# crypto_blk.net
KiCad netlist of a schematic drawn in Altium Designer
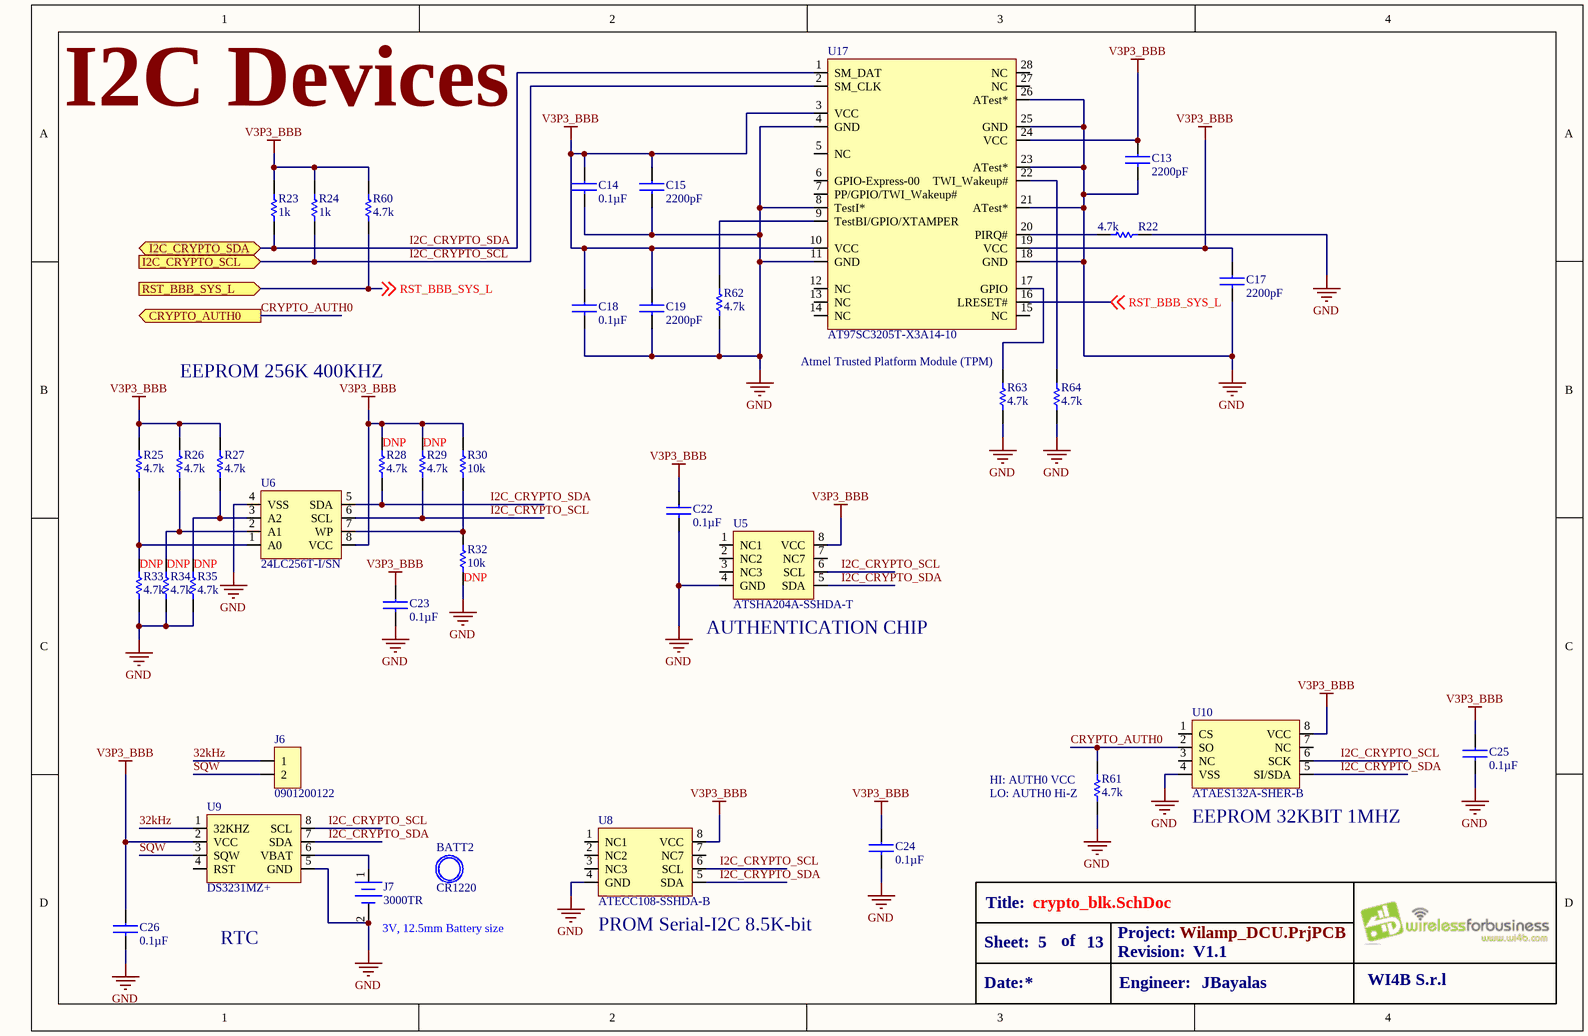
[diagram p0: crypto_blk.SchDoc]

(export (version "E")
  (design (tool "Eeschema 10.0.6"))
  (components
    (comp (ref "BATT2")
      (value "CR1220")
      (description "Coin Cell Battery 35mAh 12.5mm")
      (fields (field (name "MPN") "CR1220"))
      (libsource (lib "Miscellaneous") (part "CR1220"))
    )
    (comp (ref "C13")
      (value "2200pF")
      (footprint "C0805")
      (description "CAP CER 2200PF 50V 10% X7R 0805")
      (fields (field (name "MPN") "08055C222KAT2A"))
      (libsource (lib "Capacitor") (part "08055C222KAT2A"))
    )
    (comp (ref "C14")
      (value "0.1µF")
      (footprint "C0402")
      (description "CAP CER 0.1UF 16V X7R 0402")
      (fields (field (name "MPN") "CL05B104KO3LNNC"))
      (libsource (lib "Capacitor") (part "CL05B104KO3LNNC"))
    )
    (comp (ref "C15")
      (value "2200pF")
      (footprint "C0805")
      (description "CAP CER 2200PF 50V 10% X7R 0805")
      (fields (field (name "MPN") "08055C222KAT2A"))
      (libsource (lib "Capacitor") (part "08055C222KAT2A"))
    )
    (comp (ref "C17")
      (value "2200pF")
      (footprint "C0603")
      (description "CAP CER 2200PF 50V X7R 0603")
      (fields (field (name "MPN") "C0603C222K5RACTU"))
      (libsource (lib "Capacitor") (part "C0603C222K5RACTU"))
    )
    (comp (ref "C18")
      (value "0.1µF")
      (footprint "C0402")
      (description "CAP CER 0.1UF 16V X7R 0402")
      (fields (field (name "MPN") "CL05B104KO3LNNC"))
      (libsource (lib "Capacitor") (part "CL05B104KO3LNNC"))
    )
    (comp (ref "C19")
      (value "2200pF")
      (footprint "C0805")
      (description "CAP CER 2200PF 50V 10% X7R 0805")
      (fields (field (name "MPN") "08055C222KAT2A"))
      (libsource (lib "Capacitor") (part "08055C222KAT2A"))
    )
    (comp (ref "C22")
      (value "0.1µF")
      (footprint "C0402")
      (description "CAP CER 0.1UF 16V X7R 0402")
      (fields (field (name "MPN") "CL05B104KO3LNNC"))
      (libsource (lib "Capacitor") (part "CL05B104KO3LNNC"))
    )
    (comp (ref "C23")
      (value "0.1µF")
      (footprint "C0402")
      (description "CAP CER 0.1UF 16V X7R 0402")
      (fields (field (name "MPN") "CL05B104KO3LNNC"))
      (libsource (lib "Capacitor") (part "CL05B104KO3LNNC"))
    )
    (comp (ref "C24")
      (value "0.1µF")
      (footprint "C0402")
      (description "CAP CER 0.1UF 16V X7R 0402")
      (fields (field (name "MPN") "CL05B104KO3LNNC"))
      (libsource (lib "Capacitor") (part "CL05B104KO3LNNC"))
    )
    (comp (ref "C25")
      (value "0.1µF")
      (footprint "C0402")
      (description "CAP CER 0.1UF 16V X7R 0402")
      (fields (field (name "MPN") "CL05B104KO3LNNC"))
      (libsource (lib "Capacitor") (part "CL05B104KO3LNNC"))
    )
    (comp (ref "C26")
      (value "0.1µF")
      (footprint "C0402")
      (description "CAP CER 0.1UF 16V X7R 0402")
      (fields (field (name "MPN") "CL05B104KO3LNNC"))
      (libsource (lib "Capacitor") (part "CL05B104KO3LNNC"))
    )
    (comp (ref "J6")
      (value "*")
      (footprint "0901200122")
      (description "CONN HEADER 2POS .100\" STR TIN")
      (fields (field (name "MPN") "0901200122"))
      (libsource (lib "Connector") (part "0901200122"))
    )
    (comp (ref "J7")
      (value "3000TR")
      (footprint "3000TR")
      (description "Coin Cell Battery Holders SM COIN CELL B/H")
      (libsource (lib "Connector") (part "3000TR"))
    )
    (comp (ref "R22")
      (value "4.7k")
      (footprint "R0402")
      (description "RES SMD 4.7K OHM 5% 1/16W 0402")
      (fields (field (name "MPN") "RC0402JR-074K7L"))
      (libsource (lib "Res") (part "RC0402JR-074K7L"))
    )
    (comp (ref "R23")
      (value "1k")
      (footprint "R0402")
      (description "RES SMD 1K OHM 1% 1/10W 0402")
      (fields (field (name "MPN") "MCS04020C1001FE000"))
      (libsource (lib "Res") (part "MCS04020C1001FE000"))
    )
    (comp (ref "R24")
      (value "1k")
      (footprint "R0402")
      (description "RES SMD 1K OHM 1% 1/10W 0402")
      (fields (field (name "MPN") "MCS04020C1001FE000"))
      (libsource (lib "Res") (part "MCS04020C1001FE000"))
    )
    (comp (ref "R25")
      (value "4.7k")
      (footprint "R0402")
      (description "RES SMD 4.7K OHM 5% 1/16W 0402")
      (fields (field (name "MPN") "RC0402JR-074K7L"))
      (libsource (lib "Res") (part "RC0402JR-074K7L"))
    )
    (comp (ref "R26")
      (value "4.7k")
      (footprint "R0402")
      (description "RES SMD 4.7K OHM 5% 1/16W 0402")
      (fields (field (name "MPN") "RC0402JR-074K7L"))
      (libsource (lib "Res") (part "RC0402JR-074K7L"))
    )
    (comp (ref "R27")
      (value "4.7k")
      (footprint "R0402")
      (description "RES SMD 4.7K OHM 5% 1/16W 0402")
      (fields (field (name "MPN") "RC0402JR-074K7L"))
      (libsource (lib "Res") (part "RC0402JR-074K7L"))
    )
    (comp (ref "R28")
      (value "4.7k")
      (footprint "R0402")
      (description "RES SMD 4.7K OHM 5% 1/16W 0402")
      (fields (field (name "MPN") "RC0402JR-074K7L") (field (name "LOAD") "DNP"))
      (libsource (lib "Res") (part "RC0402JR-074K7L"))
    )
    (comp (ref "R29")
      (value "4.7k")
      (footprint "R0402")
      (description "RES SMD 4.7K OHM 5% 1/16W 0402")
      (fields (field (name "MPN") "RC0402JR-074K7L") (field (name "LOAD") "DNP"))
      (libsource (lib "Res") (part "RC0402JR-074K7L"))
    )
    (comp (ref "R30")
      (value "10k")
      (footprint "R0402")
      (description "RES SMD 10K OHM 1% 1/5W 0402")
      (fields (field (name "MPN") "CRCW040210K0FKEDHP"))
      (libsource (lib "Res") (part "CRCW040210K0FKEDHP"))
    )
    (comp (ref "R32")
      (value "10k")
      (footprint "R0402")
      (description "RES SMD 10K OHM 1% 1/5W 0402")
      (fields (field (name "MPN") "CRCW040210K0FKEDHP") (field (name "LOAD") "DNP"))
      (libsource (lib "Res") (part "CRCW040210K0FKEDHP"))
    )
    (comp (ref "R33")
      (value "4.7k")
      (footprint "R0402")
      (description "RES SMD 4.7K OHM 5% 1/16W 0402")
      (fields (field (name "MPN") "RC0402JR-074K7L") (field (name "LOAD") "DNP"))
      (libsource (lib "Res") (part "RC0402JR-074K7L"))
    )
    (comp (ref "R34")
      (value "4.7k")
      (footprint "R0402")
      (description "RES SMD 4.7K OHM 5% 1/16W 0402")
      (fields (field (name "MPN") "RC0402JR-074K7L") (field (name "LOAD") "DNP"))
      (libsource (lib "Res") (part "RC0402JR-074K7L"))
    )
    (comp (ref "R35")
      (value "4.7k")
      (footprint "R0402")
      (description "RES SMD 4.7K OHM 5% 1/16W 0402")
      (fields (field (name "MPN") "RC0402JR-074K7L") (field (name "LOAD") "DNP"))
      (libsource (lib "Res") (part "RC0402JR-074K7L"))
    )
    (comp (ref "R60")
      (value "4.7k")
      (footprint "R0402")
      (description "RES SMD 4.7K OHM 5% 1/16W 0402")
      (fields (field (name "MPN") "RC0402JR-074K7L"))
      (libsource (lib "Res") (part "RC0402JR-074K7L"))
    )
    (comp (ref "R61")
      (value "4.7k")
      (footprint "R0402")
      (description "RES SMD 4.7K OHM 5% 1/16W 0402")
      (fields (field (name "MPN") "RC0402JR-074K7L"))
      (libsource (lib "Res") (part "RC0402JR-074K7L"))
    )
    (comp (ref "R62")
      (value "4.7k")
      (footprint "R0402")
      (description "RES SMD 4.7K OHM 5% 1/16W 0402")
      (fields (field (name "MPN") "RC0402JR-074K7L"))
      (libsource (lib "Res") (part "RC0402JR-074K7L"))
    )
    (comp (ref "R63")
      (value "4.7k")
      (footprint "R0402")
      (description "RES SMD 4.7K OHM 5% 1/16W 0402")
      (fields (field (name "MPN") "RC0402JR-074K7L"))
      (libsource (lib "Res") (part "RC0402JR-074K7L"))
    )
    (comp (ref "R64")
      (value "4.7k")
      (footprint "R0402")
      (description "RES SMD 4.7K OHM 5% 1/16W 0402")
      (fields (field (name "MPN") "RC0402JR-074K7L"))
      (libsource (lib "Res") (part "RC0402JR-074K7L"))
    )
    (comp (ref "U5")
      (value "ATSHA204A-SSHDA-T")
      (footprint "SOIC-8")
      (description "IC AUTHENTICATION CHIP 8SOIC")
      (libsource (lib "IC") (part "ATSHA204A-SSHDA-T"))
    )
    (comp (ref "U6")
      (value "24LC256T-I/SN")
      (footprint "SOIC-8")
      (description "IC EEPROM 256K I2C 400KHZ 8SOIC")
      (libsource (lib "IC") (part "24LC256T-I/SN"))
    )
    (comp (ref "U8")
      (value "ATECC108-SSHDA-B")
      (footprint "SOIC-8")
      (description "EEPROM Serial-I2C 8.5K-bit 2.5V/3.3V/5V 8-Pin SOIC Bulk")
      (libsource (lib "IC") (part "ATECC108-SSHDA-B"))
    )
    (comp (ref "U9")
      (value "DS3231MZ+")
      (footprint "SOIC-8")
      (description "IC RTC I2C 8SOIC")
      (libsource (lib "IC") (part "DS3231MZ+"))
    )
    (comp (ref "U10")
      (value "ATAES132A-SHER-B")
      (footprint "SOIC-8")
      (description "IC EEPROM 32KBIT 1MHZ 8SOIC")
      (libsource (lib "IC") (part "ATAES132A-SHER-B"))
    )
    (comp (ref "U17")
      (value "AT97SC3205T-X3A14-10")
      (footprint "TSSOP-28")
      (description "STD COM 12C TPM 4.4 MM TSSOP UEK")
      (libsource (lib "IC") (part "AT97SC3205T-X3A14-10"))
    )
  )
  (nets
    (net (code "1") (name "/32kHz") (class "Default")
      (node (ref "J6") (pin "1") (pinfunction "1_1") (pintype "passive"))
      (node (ref "U9") (pin "1") (pinfunction "32KHZ_1") (pintype "passive"))
    )
    (net (code "2") (name "/CRYPTO_AUTH0") (class "Default")
      (node (ref "R61") (pin "2") (pinfunction "2_2") (pintype "passive"))
      (node (ref "U10") (pin "2") (pinfunction "SO_2") (pintype "passive"))
    )
    (net (code "3") (name "/I2C_CRYPTO_SCL") (class "Default")
      (node (ref "R24") (pin "2") (pinfunction "2_2") (pintype "passive"))
      (node (ref "R29") (pin "1") (pinfunction "1_1") (pintype "passive"))
      (node (ref "U10") (pin "6") (pinfunction "SCK_6") (pintype "passive"))
      (node (ref "U17") (pin "2") (pinfunction "SM_CLK_2") (pintype "passive"))
      (node (ref "U5") (pin "6") (pinfunction "SCL_6") (pintype "passive"))
      (node (ref "U6") (pin "6") (pinfunction "SCL_6") (pintype "passive"))
      (node (ref "U8") (pin "6") (pinfunction "SCL_6") (pintype "passive"))
      (node (ref "U9") (pin "8") (pinfunction "SCL_8") (pintype "passive"))
    )
    (net (code "4") (name "/I2C_CRYPTO_SDA") (class "Default")
      (node (ref "R23") (pin "2") (pinfunction "2_2") (pintype "passive"))
      (node (ref "R28") (pin "1") (pinfunction "1_1") (pintype "passive"))
      (node (ref "U10") (pin "5") (pinfunction "SI/SDA_5") (pintype "passive"))
      (node (ref "U17") (pin "1") (pinfunction "SM_DAT_1") (pintype "passive"))
      (node (ref "U5") (pin "5") (pinfunction "SDA_5") (pintype "passive"))
      (node (ref "U6") (pin "5") (pinfunction "SDA_5") (pintype "passive"))
      (node (ref "U8") (pin "5") (pinfunction "SDA_5") (pintype "passive"))
      (node (ref "U9") (pin "7") (pinfunction "SDA_7") (pintype "passive"))
    )
    (net (code "5") (name "/SQW") (class "Default")
      (node (ref "J6") (pin "2") (pinfunction "2_2") (pintype "passive"))
      (node (ref "U9") (pin "3") (pinfunction "SQW_3") (pintype "passive"))
    )
    (net (code "6") (name "GND") (class "Default")
      (node (ref "C13") (pin "2") (pinfunction "2_2") (pintype "passive"))
      (node (ref "C14") (pin "2") (pinfunction "2_2") (pintype "passive"))
      (node (ref "C15") (pin "2") (pinfunction "2_2") (pintype "passive"))
      (node (ref "C17") (pin "2") (pinfunction "2_2") (pintype "passive"))
      (node (ref "C18") (pin "2") (pinfunction "2_2") (pintype "passive"))
      (node (ref "C19") (pin "2") (pinfunction "2_2") (pintype "passive"))
      (node (ref "C22") (pin "2") (pinfunction "2_2") (pintype "passive"))
      (node (ref "C23") (pin "2") (pinfunction "2_2") (pintype "passive"))
      (node (ref "C24") (pin "2") (pinfunction "2_2") (pintype "passive"))
      (node (ref "C25") (pin "2") (pinfunction "2_2") (pintype "passive"))
      (node (ref "C26") (pin "2") (pinfunction "2_2") (pintype "passive"))
      (node (ref "J7") (pin "2") (pinfunction "-_2") (pintype "passive"))
      (node (ref "R22") (pin "1") (pinfunction "1_1") (pintype "passive"))
      (node (ref "R32") (pin "1") (pinfunction "1_1") (pintype "passive"))
      (node (ref "R33") (pin "1") (pinfunction "1_1") (pintype "passive"))
      (node (ref "R34") (pin "1") (pinfunction "1_1") (pintype "passive"))
      (node (ref "R35") (pin "1") (pinfunction "1_1") (pintype "passive"))
      (node (ref "R61") (pin "1") (pinfunction "1_1") (pintype "passive"))
      (node (ref "R62") (pin "1") (pinfunction "1_1") (pintype "passive"))
      (node (ref "R63") (pin "1") (pinfunction "1_1") (pintype "passive"))
      (node (ref "R64") (pin "1") (pinfunction "1_1") (pintype "passive"))
      (node (ref "U10") (pin "4") (pinfunction "VSS_4") (pintype "passive"))
      (node (ref "U17") (pin "11") (pinfunction "GND_11") (pintype "passive"))
      (node (ref "U17") (pin "18") (pinfunction "GND_18") (pintype "passive"))
      (node (ref "U17") (pin "21") (pinfunction "ATest*_21") (pintype "passive"))
      (node (ref "U17") (pin "23") (pinfunction "ATest*_23") (pintype "passive"))
      (node (ref "U17") (pin "25") (pinfunction "GND_25") (pintype "passive"))
      (node (ref "U17") (pin "26") (pinfunction "ATest*_26") (pintype "passive"))
      (node (ref "U17") (pin "4") (pinfunction "GND_4") (pintype "passive"))
      (node (ref "U17") (pin "8") (pinfunction "TestI*_8") (pintype "passive"))
      (node (ref "U5") (pin "4") (pinfunction "GND_4") (pintype "passive"))
      (node (ref "U6") (pin "4") (pinfunction "VSS_4") (pintype "passive"))
      (node (ref "U8") (pin "4") (pinfunction "GND_4") (pintype "passive"))
      (node (ref "U9") (pin "5") (pinfunction "GND_5") (pintype "passive"))
    )
    (net (code "7") (name "Net-(J7-+)") (class "Default")
      (node (ref "J7") (pin "1") (pinfunction "+_1") (pintype "passive"))
      (node (ref "U9") (pin "6") (pinfunction "VBAT_6") (pintype "passive"))
    )
    (net (code "8") (name "Net-(U6-A0)") (class "Default")
      (node (ref "R25") (pin "1") (pinfunction "1_1") (pintype "passive"))
      (node (ref "R33") (pin "2") (pinfunction "2_2") (pintype "passive"))
      (node (ref "U6") (pin "1") (pinfunction "A0_1") (pintype "passive"))
    )
    (net (code "9") (name "Net-(U6-A1)") (class "Default")
      (node (ref "R26") (pin "1") (pinfunction "1_1") (pintype "passive"))
      (node (ref "R34") (pin "2") (pinfunction "2_2") (pintype "passive"))
      (node (ref "U6") (pin "2") (pinfunction "A1_2") (pintype "passive"))
    )
    (net (code "10") (name "Net-(U6-A2)") (class "Default")
      (node (ref "R27") (pin "1") (pinfunction "1_1") (pintype "passive"))
      (node (ref "R35") (pin "2") (pinfunction "2_2") (pintype "passive"))
      (node (ref "U6") (pin "3") (pinfunction "A2_3") (pintype "passive"))
    )
    (net (code "11") (name "Net-(U6-WP)") (class "Default")
      (node (ref "R30") (pin "1") (pinfunction "1_1") (pintype "passive"))
      (node (ref "R32") (pin "2") (pinfunction "2_2") (pintype "passive"))
      (node (ref "U6") (pin "7") (pinfunction "WP_7") (pintype "passive"))
    )
    (net (code "12") (name "Net-(U17-GPIO)") (class "Default")
      (node (ref "R63") (pin "2") (pinfunction "2_2") (pintype "passive"))
      (node (ref "U17") (pin "17") (pinfunction "GPIO_17") (pintype "passive"))
    )
    (net (code "13") (name "Net-(U17-PIRQ#)") (class "Default")
      (node (ref "R22") (pin "2") (pinfunction "2_2") (pintype "passive"))
      (node (ref "U17") (pin "20") (pinfunction "PIRQ#_20") (pintype "passive"))
    )
    (net (code "14") (name "Net-(U17-TWI_Wakeup#)") (class "Default")
      (node (ref "R64") (pin "2") (pinfunction "2_2") (pintype "passive"))
      (node (ref "U17") (pin "22") (pinfunction "TWI_Wakeup#_22") (pintype "passive"))
    )
    (net (code "15") (name "Net-(U17-TestBI{slash}GPIO{slash}XTAMPER)") (class "Default")
      (node (ref "R62") (pin "2") (pinfunction "2_2") (pintype "passive"))
      (node (ref "U17") (pin "9") (pinfunction "TestBI/GPIO/XTAMPER_9") (pintype "passive"))
    )
    (net (code "16") (name "RST_BBB_SYS_L") (class "Default")
      (node (ref "R60") (pin "1") (pinfunction "1_1") (pintype "passive"))
      (node (ref "U17") (pin "16") (pinfunction "LRESET#_16") (pintype "passive"))
    )
    (net (code "17") (name "V3P3_BBB") (class "Default")
      (node (ref "C13") (pin "1") (pinfunction "1_1") (pintype "passive"))
      (node (ref "C14") (pin "1") (pinfunction "1_1") (pintype "passive"))
      (node (ref "C15") (pin "1") (pinfunction "1_1") (pintype "passive"))
      (node (ref "C17") (pin "1") (pinfunction "1_1") (pintype "passive"))
      (node (ref "C18") (pin "1") (pinfunction "1_1") (pintype "passive"))
      (node (ref "C19") (pin "1") (pinfunction "1_1") (pintype "passive"))
      (node (ref "C22") (pin "1") (pinfunction "1_1") (pintype "passive"))
      (node (ref "C23") (pin "1") (pinfunction "1_1") (pintype "passive"))
      (node (ref "C24") (pin "1") (pinfunction "1_1") (pintype "passive"))
      (node (ref "C25") (pin "1") (pinfunction "1_1") (pintype "passive"))
      (node (ref "C26") (pin "1") (pinfunction "1_1") (pintype "passive"))
      (node (ref "R23") (pin "1") (pinfunction "1_1") (pintype "passive"))
      (node (ref "R24") (pin "1") (pinfunction "1_1") (pintype "passive"))
      (node (ref "R25") (pin "2") (pinfunction "2_2") (pintype "passive"))
      (node (ref "R26") (pin "2") (pinfunction "2_2") (pintype "passive"))
      (node (ref "R27") (pin "2") (pinfunction "2_2") (pintype "passive"))
      (node (ref "R28") (pin "2") (pinfunction "2_2") (pintype "passive"))
      (node (ref "R29") (pin "2") (pinfunction "2_2") (pintype "passive"))
      (node (ref "R30") (pin "2") (pinfunction "2_2") (pintype "passive"))
      (node (ref "R60") (pin "2") (pinfunction "2_2") (pintype "passive"))
      (node (ref "U10") (pin "8") (pinfunction "VCC_8") (pintype "passive"))
      (node (ref "U17") (pin "10") (pinfunction "VCC_10") (pintype "passive"))
      (node (ref "U17") (pin "19") (pinfunction "VCC_19") (pintype "passive"))
      (node (ref "U17") (pin "24") (pinfunction "VCC_24") (pintype "passive"))
      (node (ref "U17") (pin "3") (pinfunction "VCC_3") (pintype "passive"))
      (node (ref "U5") (pin "8") (pinfunction "VCC_8") (pintype "passive"))
      (node (ref "U6") (pin "8") (pinfunction "VCC_8") (pintype "passive"))
      (node (ref "U8") (pin "8") (pinfunction "VCC_8") (pintype "passive"))
      (node (ref "U9") (pin "2") (pinfunction "VCC_2") (pintype "passive"))
    )
    (net (code "18") (name "unconnected-(U5-NC1-Pad1)") (class "Default")
      (node (ref "U5") (pin "1") (pinfunction "NC1_1") (pintype "passive"))
    )
    (net (code "19") (name "unconnected-(U5-NC2-Pad2)") (class "Default")
      (node (ref "U5") (pin "2") (pinfunction "NC2_2") (pintype "passive"))
    )
    (net (code "20") (name "unconnected-(U5-NC3-Pad3)") (class "Default")
      (node (ref "U5") (pin "3") (pinfunction "NC3_3") (pintype "passive"))
    )
    (net (code "21") (name "unconnected-(U5-NC7-Pad7)") (class "Default")
      (node (ref "U5") (pin "7") (pinfunction "NC7_7") (pintype "passive"))
    )
    (net (code "22") (name "unconnected-(U8-NC1-Pad1)") (class "Default")
      (node (ref "U8") (pin "1") (pinfunction "NC1_1") (pintype "passive"))
    )
    (net (code "23") (name "unconnected-(U8-NC2-Pad2)") (class "Default")
      (node (ref "U8") (pin "2") (pinfunction "NC2_2") (pintype "passive"))
    )
    (net (code "24") (name "unconnected-(U8-NC3-Pad3)") (class "Default")
      (node (ref "U8") (pin "3") (pinfunction "NC3_3") (pintype "passive"))
    )
    (net (code "25") (name "unconnected-(U8-NC7-Pad7)") (class "Default")
      (node (ref "U8") (pin "7") (pinfunction "NC7_7") (pintype "passive"))
    )
    (net (code "26") (name "unconnected-(U9-RST-Pad4)") (class "Default")
      (node (ref "U9") (pin "4") (pinfunction "RST_4") (pintype "passive"))
    )
    (net (code "27") (name "unconnected-(U10-CS-Pad1)") (class "Default")
      (node (ref "U10") (pin "1") (pinfunction "CS_1") (pintype "passive"))
    )
    (net (code "28") (name "unconnected-(U10-NC-Pad3)") (class "Default")
      (node (ref "U10") (pin "3") (pinfunction "NC_3") (pintype "passive"))
    )
    (net (code "29") (name "unconnected-(U10-NC-Pad7)") (class "Default")
      (node (ref "U10") (pin "7") (pinfunction "NC_7") (pintype "passive"))
    )
    (net (code "30") (name "unconnected-(U17-GPIO-Express-00-Pad6)") (class "Default")
      (node (ref "U17") (pin "6") (pinfunction "GPIO-Express-00_6") (pintype "passive"))
    )
    (net (code "31") (name "unconnected-(U17-NC-Pad5)") (class "Default")
      (node (ref "U17") (pin "5") (pinfunction "NC_5") (pintype "passive"))
    )
    (net (code "32") (name "unconnected-(U17-NC-Pad12)") (class "Default")
      (node (ref "U17") (pin "12") (pinfunction "NC_12") (pintype "passive"))
    )
    (net (code "33") (name "unconnected-(U17-NC-Pad13)") (class "Default")
      (node (ref "U17") (pin "13") (pinfunction "NC_13") (pintype "passive"))
    )
    (net (code "34") (name "unconnected-(U17-NC-Pad14)") (class "Default")
      (node (ref "U17") (pin "14") (pinfunction "NC_14") (pintype "passive"))
    )
    (net (code "35") (name "unconnected-(U17-NC-Pad15)") (class "Default")
      (node (ref "U17") (pin "15") (pinfunction "NC_15") (pintype "passive"))
    )
    (net (code "36") (name "unconnected-(U17-NC-Pad27)") (class "Default")
      (node (ref "U17") (pin "27") (pinfunction "NC_27") (pintype "passive"))
    )
    (net (code "37") (name "unconnected-(U17-NC-Pad28)") (class "Default")
      (node (ref "U17") (pin "28") (pinfunction "NC_28") (pintype "passive"))
    )
    (net (code "38") (name "unconnected-(U17-PP{slash}GPIO{slash}TWI_Wakeup#-Pad7)") (class "Default")
      (node (ref "U17") (pin "7") (pinfunction "PP/GPIO/TWI_Wakeup#_7") (pintype "passive"))
    )
  )
)
